# IR_blinker.net
KiCad netlist of a schematic drawn in EAGLE
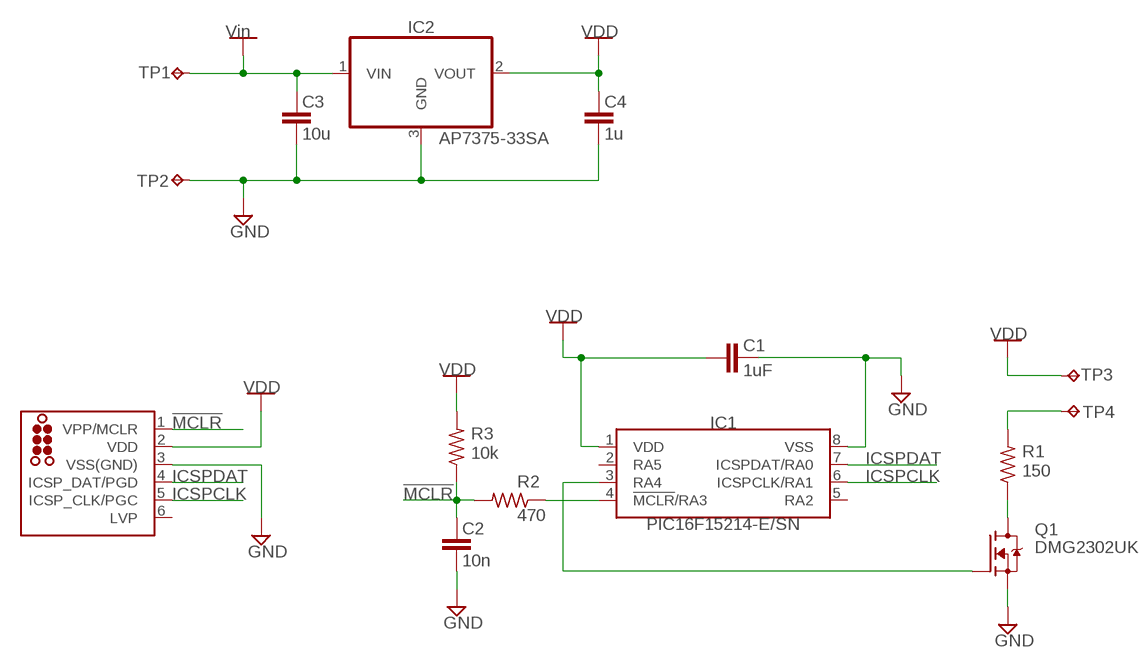
[diagram p0: schematic, sheet 1]

(export (version "E")
  (design (tool "Eeschema 10.0.6"))
  (components
    (comp (ref "C1")
      (value "1uF")
      (footprint "eagle-import:C0603")
      (libsource (lib "eagle-import") (part "C-EUC0603"))
    )
    (comp (ref "C2")
      (value "10n")
      (footprint "eagle-import:C0603")
      (libsource (lib "eagle-import") (part "C-EUC0603"))
    )
    (comp (ref "C3")
      (value "10u")
      (footprint "eagle-import:C0603")
      (libsource (lib "eagle-import") (part "C-EUC0603"))
    )
    (comp (ref "C4")
      (value "1u")
      (footprint "eagle-import:C0603")
      (libsource (lib "eagle-import") (part "C-EUC0603"))
    )
    (comp (ref "IC1")
      (value "PIC16F15214-E/SN")
      (footprint "eagle-import:SOIC-8")
      (libsource (lib "eagle-import") (part "PIC16F15214-E/SN"))
    )
    (comp (ref "IC2")
      (value "AP7375-33SA")
      (footprint "eagle-import:SOT23")
      (libsource (lib "eagle-import") (part "AP7375-33SA"))
    )
    (comp (ref "J1")
      (value "TC2030-MCP-NL")
      (footprint "eagle-import:TC2030-MCP-NL")
      (libsource (lib "eagle-import") (part "TC2030-MCP-NL"))
    )
    (comp (ref "Q1")
      (value "DMG2302UK")
      (footprint "eagle-import:SOT23")
      (libsource (lib "eagle-import") (part "DMG2302UK"))
    )
    (comp (ref "R1")
      (value "150")
      (footprint "eagle-import:R0603")
      (libsource (lib "eagle-import") (part "R-US_R0603"))
    )
    (comp (ref "R2")
      (value "470")
      (footprint "eagle-import:R0603")
      (libsource (lib "eagle-import") (part "R-US_R0603"))
    )
    (comp (ref "R3")
      (value "10k")
      (footprint "eagle-import:R0603")
      (libsource (lib "eagle-import") (part "R-US_R0603"))
    )
    (comp (ref "TP1")
      (value "TPTP20SQ")
      (footprint "eagle-import:TP20SQ")
      (libsource (lib "eagle-import") (part "TPTP20SQ"))
    )
    (comp (ref "TP2")
      (value "TPTP20SQ")
      (footprint "eagle-import:TP20SQ")
      (libsource (lib "eagle-import") (part "TPTP20SQ"))
    )
    (comp (ref "TP3")
      (value "TPTP20SQ")
      (footprint "eagle-import:TP20SQ")
      (libsource (lib "eagle-import") (part "TPTP20SQ"))
    )
    (comp (ref "TP4")
      (value "TPTP20SQ")
      (footprint "eagle-import:TP20SQ")
      (libsource (lib "eagle-import") (part "TPTP20SQ"))
    )
  )
  (nets
    (net (code "1") (name "/ICSPCLK") (class "Default")
      (node (ref "IC1") (pin "6") (pinfunction "ICSPCLK/RA1_6") (pintype "bidirectional"))
      (node (ref "J1") (pin "5") (pinfunction "ICSP_CLK/PGC_5") (pintype "output"))
    )
    (net (code "2") (name "/ICSPDAT") (class "Default")
      (node (ref "IC1") (pin "7") (pinfunction "ICSPDAT/RA0_7") (pintype "bidirectional"))
      (node (ref "J1") (pin "4") (pinfunction "ICSP_DAT/PGD_4") (pintype "bidirectional"))
    )
    (net (code "3") (name "/~{MCLR}") (class "Default")
      (node (ref "C2") (pin "2") (pinfunction "2_2") (pintype "passive"))
      (node (ref "J1") (pin "1") (pinfunction "VPP/MCLR_1") (pintype "passive"))
      (node (ref "R2") (pin "2") (pinfunction "2_2") (pintype "passive"))
      (node (ref "R3") (pin "1") (pinfunction "1_1") (pintype "passive"))
    )
    (net (code "4") (name "GND") (class "Default")
      (node (ref "C1") (pin "2") (pinfunction "2_2") (pintype "passive"))
      (node (ref "C2") (pin "1") (pinfunction "1_1") (pintype "passive"))
      (node (ref "C3") (pin "1") (pinfunction "1_1") (pintype "passive"))
      (node (ref "C4") (pin "1") (pinfunction "1_1") (pintype "passive"))
      (node (ref "IC1") (pin "8") (pinfunction "VSS_8") (pintype "bidirectional"))
      (node (ref "IC2") (pin "3") (pinfunction "GND_3") (pintype "power_in"))
      (node (ref "J1") (pin "3") (pinfunction "VSS(GND)_3") (pintype "power_in"))
      (node (ref "Q1") (pin "2") (pinfunction "S_2") (pintype "passive"))
      (node (ref "TP2") (pin "TP") (pinfunction "TP_TP") (pintype "input"))
    )
    (net (code "5") (name "Net-(IC1-RA4)") (class "Default")
      (node (ref "IC1") (pin "3") (pinfunction "RA4_3") (pintype "bidirectional"))
      (node (ref "Q1") (pin "1") (pinfunction "G_1") (pintype "passive"))
    )
    (net (code "6") (name "Net-(IC1-~{MCLR}{slash}RA3)") (class "Default")
      (node (ref "IC1") (pin "4") (pinfunction "~{MCLR}/RA3_4") (pintype "bidirectional"))
      (node (ref "R2") (pin "1") (pinfunction "1_1") (pintype "passive"))
    )
    (net (code "7") (name "Net-(Q1-D)") (class "Default")
      (node (ref "Q1") (pin "3") (pinfunction "D_3") (pintype "passive"))
      (node (ref "R1") (pin "1") (pinfunction "1_1") (pintype "passive"))
    )
    (net (code "8") (name "Net-(R1-Pad2)") (class "Default")
      (node (ref "R1") (pin "2") (pinfunction "2_2") (pintype "passive"))
      (node (ref "TP4") (pin "TP") (pinfunction "TP_TP") (pintype "input"))
    )
    (net (code "9") (name "VDD") (class "Default")
      (node (ref "C1") (pin "1") (pinfunction "1_1") (pintype "passive"))
      (node (ref "C4") (pin "2") (pinfunction "2_2") (pintype "passive"))
      (node (ref "IC1") (pin "1") (pinfunction "VDD_1") (pintype "bidirectional"))
      (node (ref "IC2") (pin "2") (pinfunction "VOUT_2") (pintype "output"))
      (node (ref "J1") (pin "2") (pinfunction "VDD_2") (pintype "power_in"))
      (node (ref "R3") (pin "2") (pinfunction "2_2") (pintype "passive"))
      (node (ref "TP3") (pin "TP") (pinfunction "TP_TP") (pintype "input"))
    )
    (net (code "10") (name "Vin") (class "Default")
      (node (ref "C3") (pin "2") (pinfunction "2_2") (pintype "passive"))
      (node (ref "IC2") (pin "1") (pinfunction "VIN_1") (pintype "input"))
      (node (ref "TP1") (pin "TP") (pinfunction "TP_TP") (pintype "input"))
    )
    (net (code "11") (name "unconnected-(IC1-RA2-Pad5)") (class "Default")
      (node (ref "IC1") (pin "5") (pinfunction "RA2_5") (pintype "bidirectional"))
    )
    (net (code "12") (name "unconnected-(IC1-RA5-Pad2)") (class "Default")
      (node (ref "IC1") (pin "2") (pinfunction "RA5_2") (pintype "bidirectional"))
    )
    (net (code "13") (name "unconnected-(J1-LVP-Pad6)") (class "Default")
      (node (ref "J1") (pin "6") (pinfunction "LVP_6") (pintype "bidirectional"))
    )
  )
)
